# SOC_camera.net
KiCad netlist of a schematic drawn in EAGLE
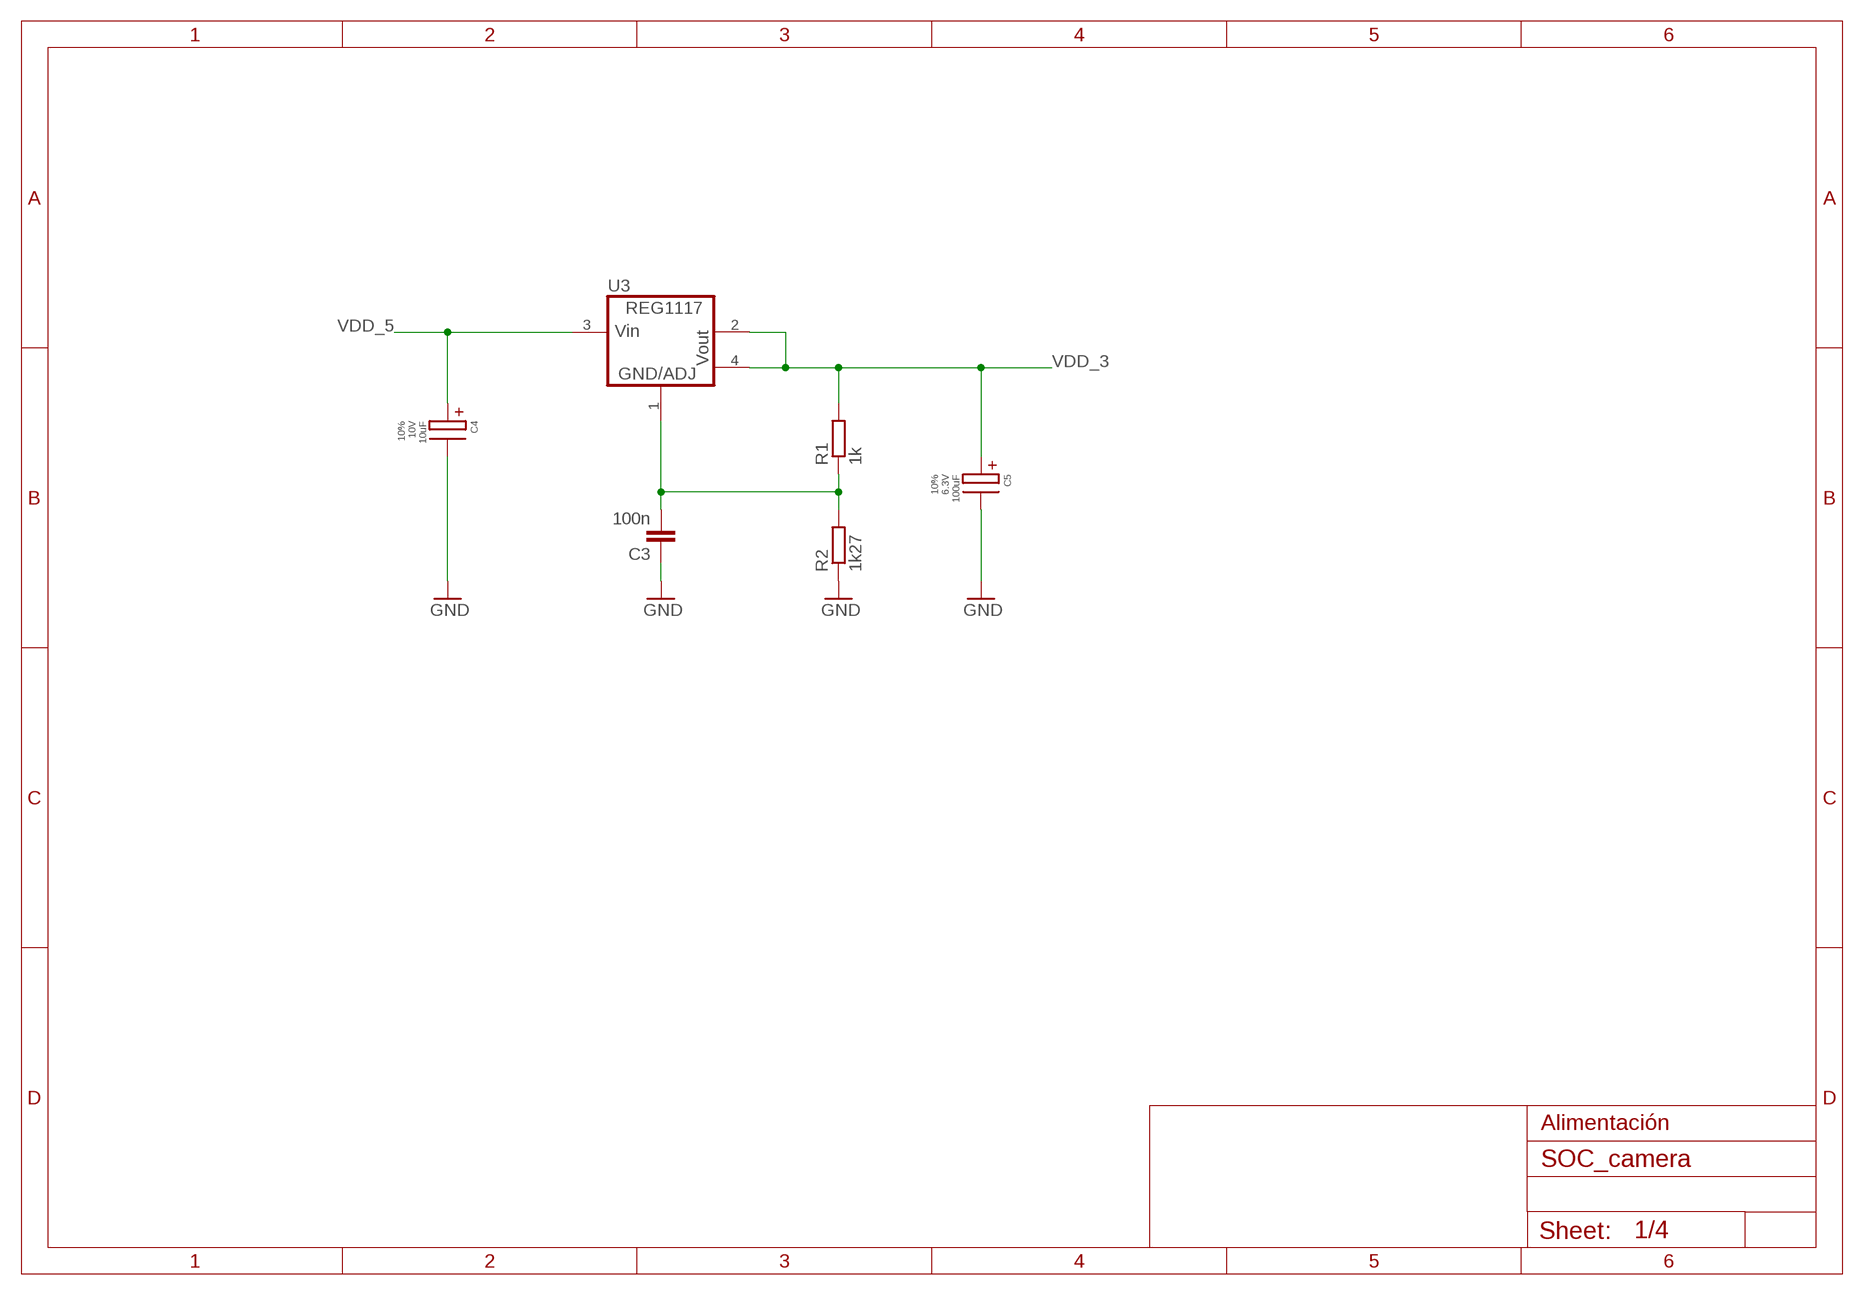
[diagram p0: schematic, sheet 1]
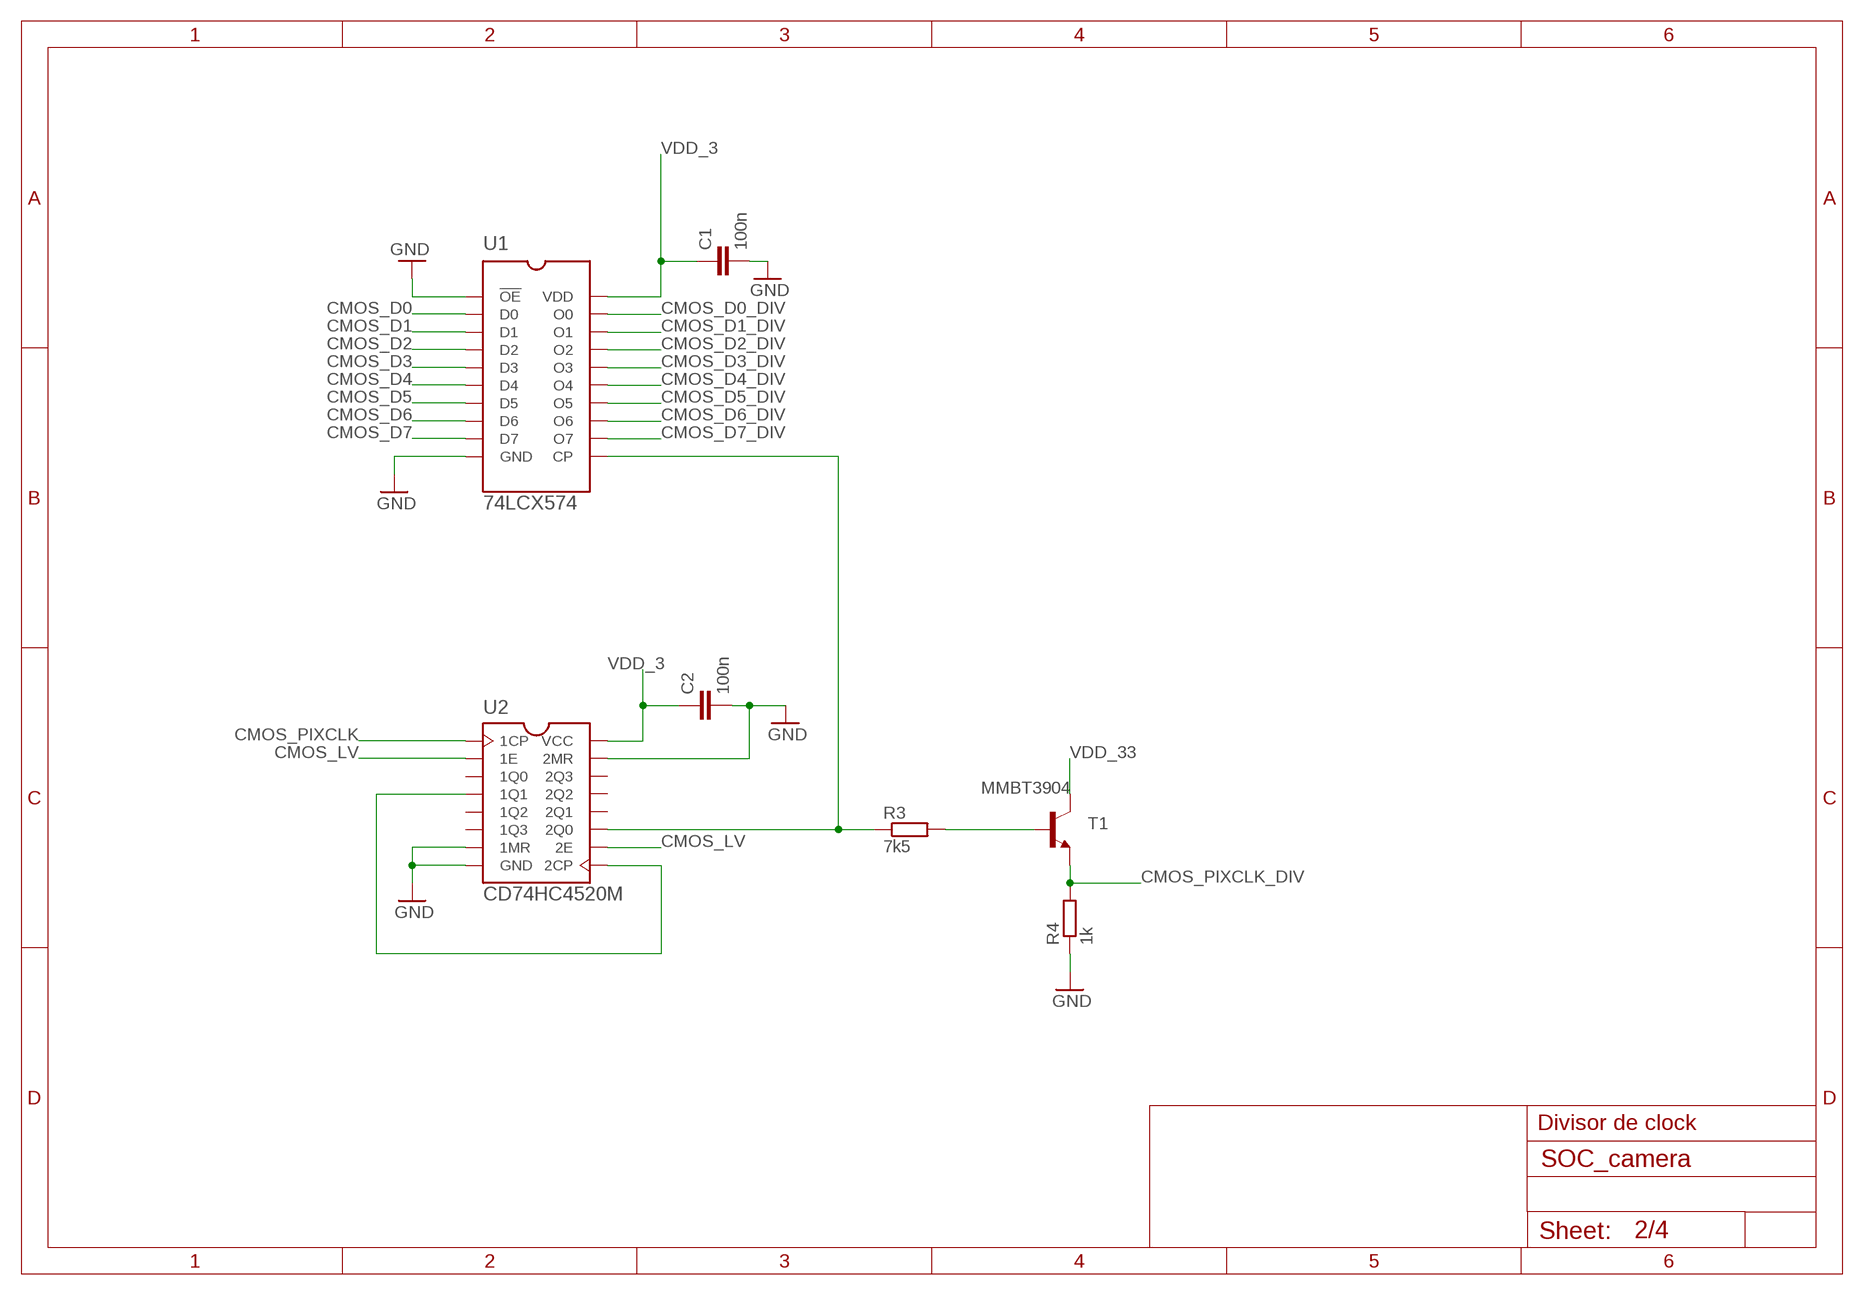
[diagram p1: schematic, sheet 2]
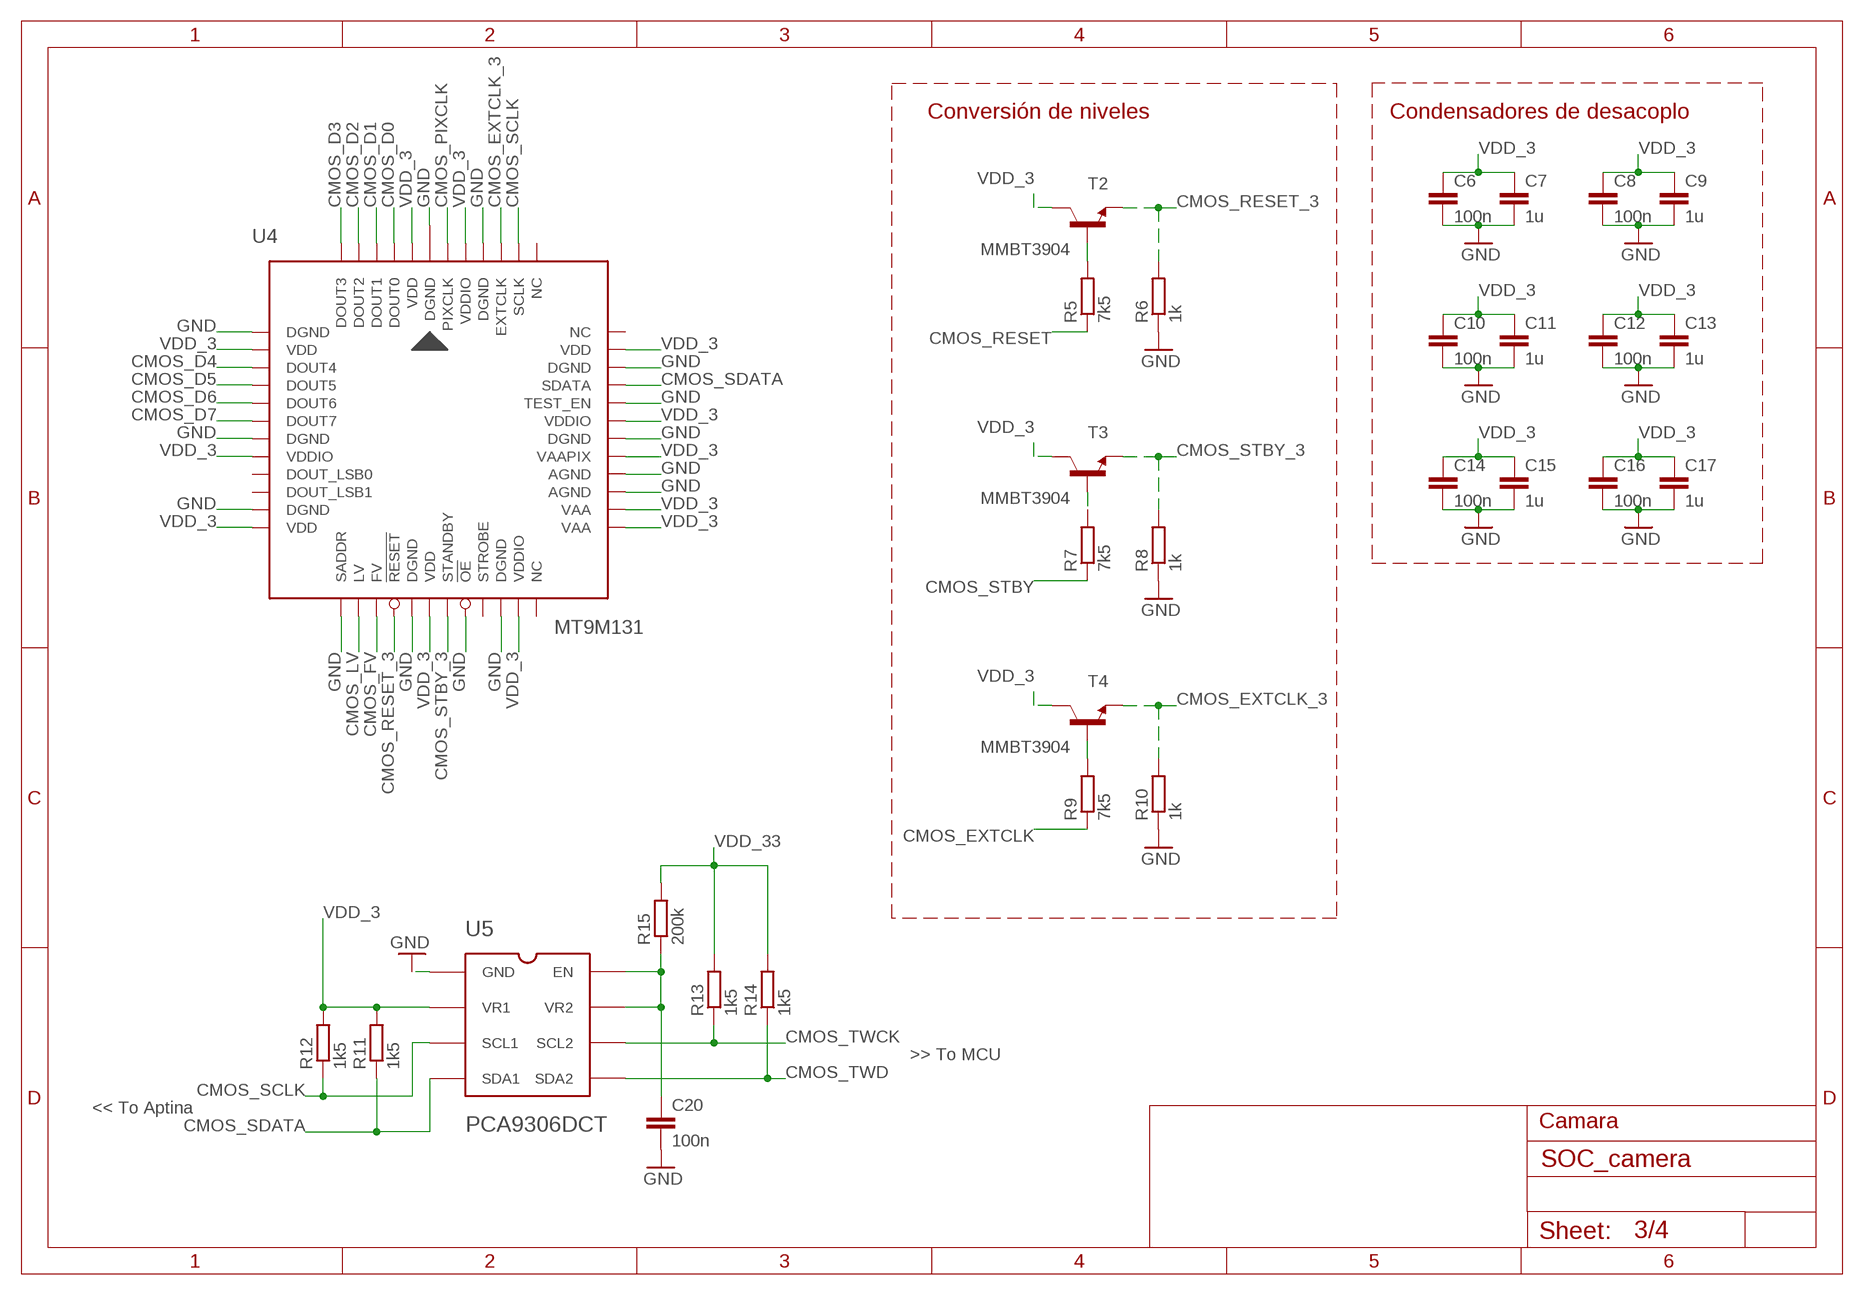
[diagram p2: schematic, sheet 3]
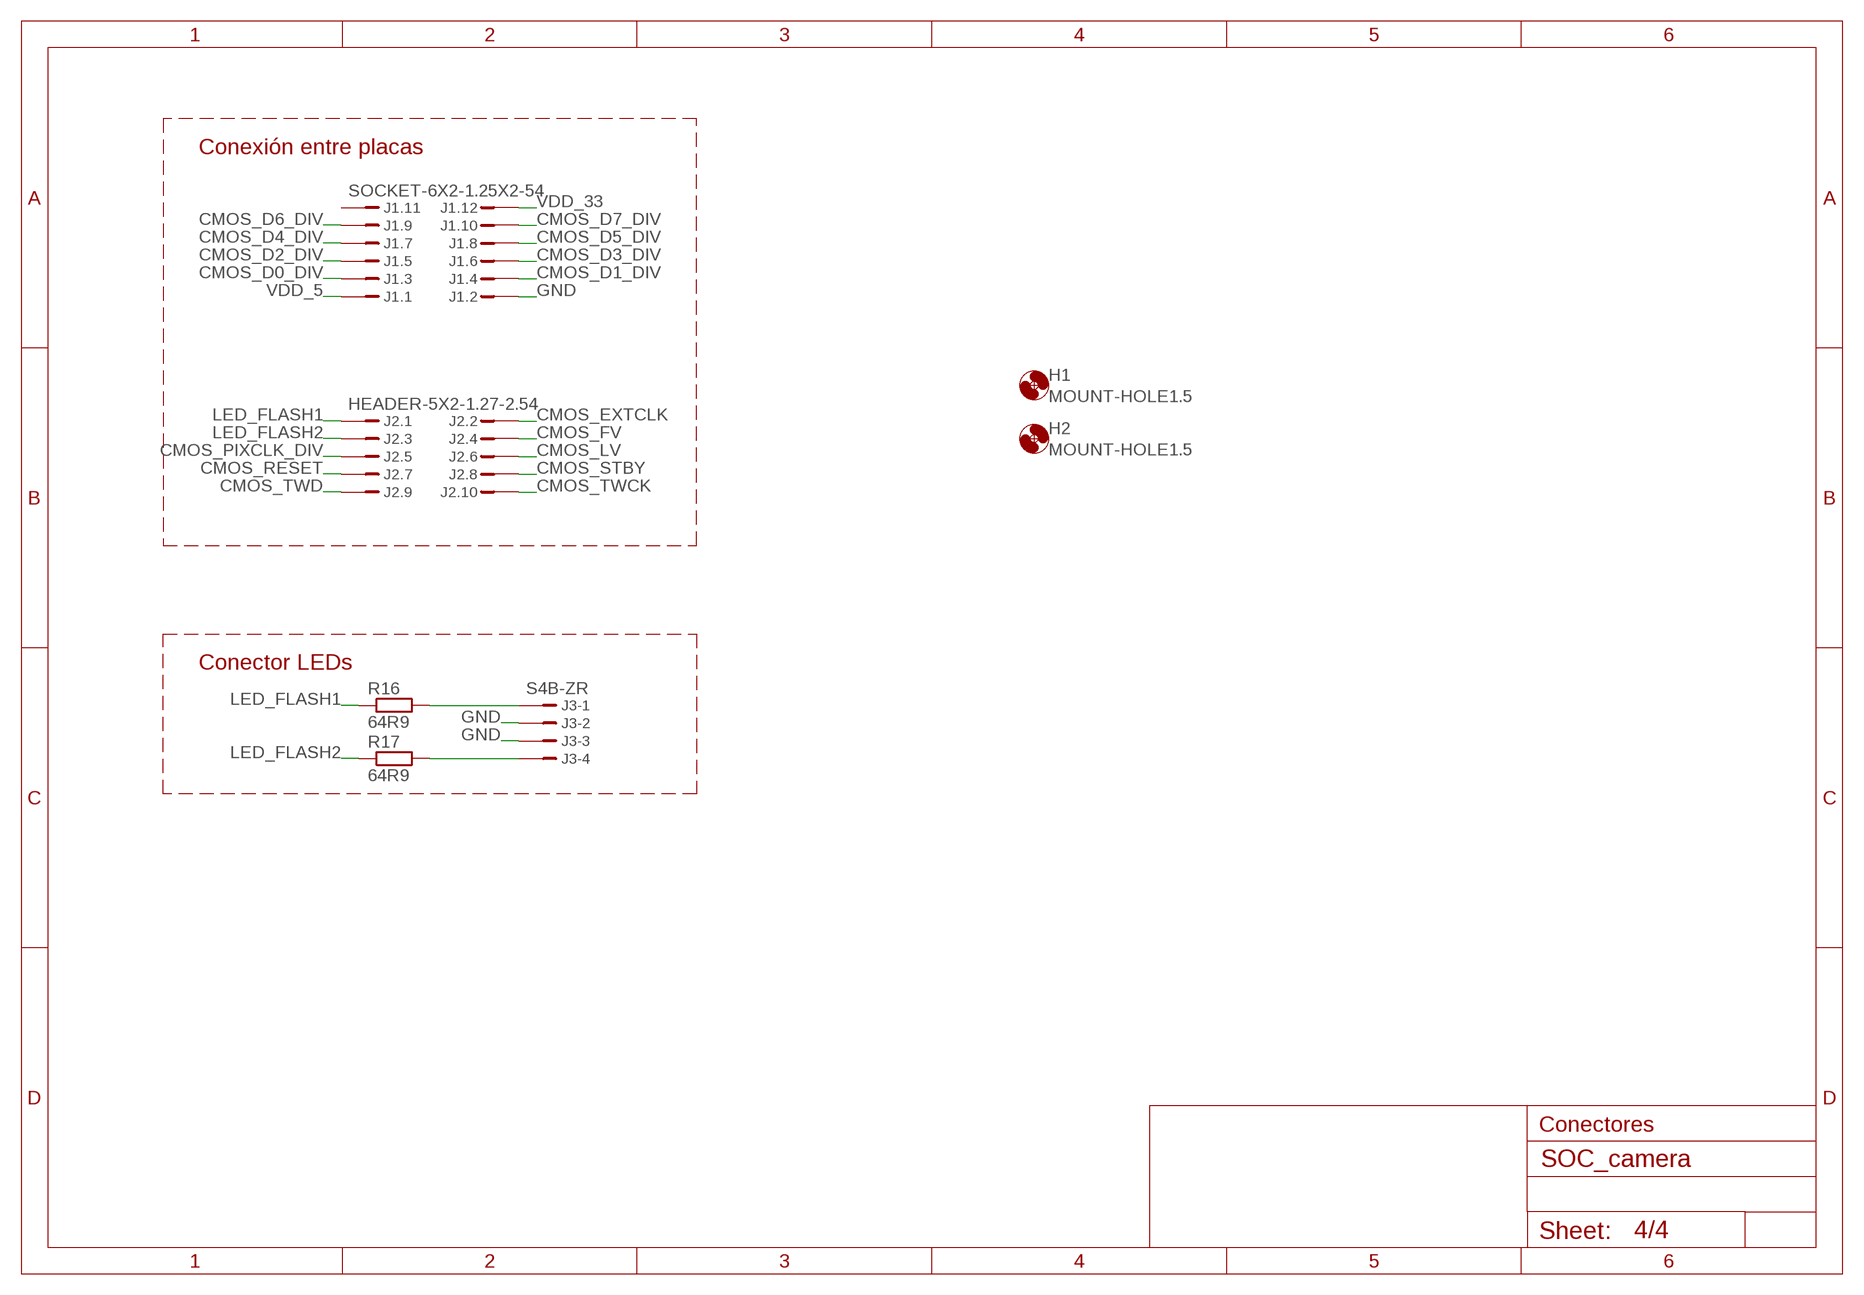
[diagram p3: schematic, sheet 4]

(export (version "E")
  (design (tool "Eeschema 10.0.6"))
  (components
    (comp (ref "C3")
      (value "100n")
      (footprint "eagle-import:C0603")
      (libsource (lib "eagle-import") (part "C-EUC0603"))
    )
    (comp (ref "C4")
      (value "10uF")
      (footprint "eagle-import:3528-21")
      (fields
        (field (name "MPN") "293D106X9010B2TE3")
        (field (name "TOLERANCE") "10%")
        (field (name "VOLTAGE") "10V")
      )
      (libsource (lib "eagle-import") (part "CPOL_TF-B10U-10V-10%-"))
    )
    (comp (ref "C5")
      (value "100uF")
      (footprint "eagle-import:3528-21")
      (fields
        (field (name "MPN") "293D107X96R3B2TE3")
        (field (name "TOLERANCE") "10%")
        (field (name "VOLTAGE") "6.3V")
      )
      (libsource (lib "eagle-import") (part "CPOL_TF-B100U-6V3-10%-"))
    )
    (comp (ref "R1")
      (value "1k")
      (footprint "eagle-import:R0603")
      (libsource (lib "eagle-import") (part "R-EU_R0603"))
    )
    (comp (ref "R2")
      (value "1k27")
      (footprint "eagle-import:R0603")
      (libsource (lib "eagle-import") (part "R-EU_R0603"))
    )
    (comp (ref "U3")
      (value "REG1117")
      (footprint "eagle-import:SOT223")
      (libsource (lib "eagle-import") (part "REG1117"))
    )
    (comp (ref "H1")
      (value "MOUNT-HOLE1.5")
      (footprint "eagle-import:1,5")
      (libsource (lib "eagle-import") (part "MOUNT-HOLE1.5"))
    )
    (comp (ref "H2")
      (value "MOUNT-HOLE1.5")
      (footprint "eagle-import:1,5")
      (libsource (lib "eagle-import") (part "MOUNT-HOLE1.5"))
    )
    (comp (ref "J1")
      (value "SOCKET-6X2-1.25X2-54")
      (footprint "eagle-import:SOCKET-THD-6X2(1.27X2.54)")
      (libsource (lib "eagle-import") (part "SOCKET-6X2-1.25X2-54"))
    )
    (comp (ref "J2")
      (value "HEADER-5X2-1.27-2.54")
      (footprint "eagle-import:HEADER-THD-5X2(1.27X2.54)")
      (libsource (lib "eagle-import") (part "HEADER-5X2-1.27-2.54"))
    )
    (comp (ref "J3")
      (value "S4B-ZR")
      (footprint "eagle-import:S4B-ZR")
      (fields (field (name "MF") "FARNELL") (field (name "MPN") "S4B-ZR(LF)(SN)"))
      (libsource (lib "eagle-import") (part "?4B-ZRS"))
    )
    (comp (ref "R16")
      (value "64R9")
      (footprint "eagle-import:R0603")
      (libsource (lib "eagle-import") (part "R-EU_R0603"))
    )
    (comp (ref "R17")
      (value "64R9")
      (footprint "eagle-import:R0603")
      (libsource (lib "eagle-import") (part "R-EU_R0603"))
    )
    (comp (ref "C1")
      (value "100n")
      (footprint "eagle-import:C0603")
      (libsource (lib "eagle-import") (part "C-EUC0603"))
    )
    (comp (ref "C2")
      (value "100n")
      (footprint "eagle-import:C0603")
      (libsource (lib "eagle-import") (part "C-EUC0603"))
    )
    (comp (ref "R3")
      (value "7k5")
      (footprint "eagle-import:R0603")
      (libsource (lib "eagle-import") (part "resistor_R-EU_R0603"))
    )
    (comp (ref "R4")
      (value "1k")
      (footprint "eagle-import:R0603")
      (libsource (lib "eagle-import") (part "resistor_R-EU_R0603"))
    )
    (comp (ref "T1")
      (value "MMBT3904")
      (footprint "eagle-import:SOT23-BEC")
      (libsource (lib "eagle-import") (part "-NPN-SOT23-BECMMBT3904LT1"))
    )
    (comp (ref "U1")
      (value "74LCX574")
      (footprint "eagle-import:TSSOP20")
      (fields (field (name "MPN") "74LCX574MTCX "))
      (libsource (lib "eagle-import") (part "74LCX574"))
    )
    (comp (ref "U2")
      (value "CD74HC4520M")
      (footprint "eagle-import:SOP16")
      (libsource (lib "eagle-import") (part "CD74HC4520M"))
    )
    (comp (ref "C6")
      (value "100n")
      (footprint "eagle-import:C0402")
      (libsource (lib "eagle-import") (part "C-EUC0402"))
    )
    (comp (ref "C7")
      (value "1u")
      (footprint "eagle-import:C0402")
      (libsource (lib "eagle-import") (part "C-EUC0402"))
    )
    (comp (ref "C8")
      (value "100n")
      (footprint "eagle-import:C0402")
      (libsource (lib "eagle-import") (part "C-EUC0402"))
    )
    (comp (ref "C9")
      (value "1u")
      (footprint "eagle-import:C0402")
      (libsource (lib "eagle-import") (part "C-EUC0402"))
    )
    (comp (ref "C10")
      (value "100n")
      (footprint "eagle-import:C0402")
      (libsource (lib "eagle-import") (part "C-EUC0402"))
    )
    (comp (ref "C11")
      (value "1u")
      (footprint "eagle-import:C0402")
      (libsource (lib "eagle-import") (part "C-EUC0402"))
    )
    (comp (ref "C12")
      (value "100n")
      (footprint "eagle-import:C0402")
      (libsource (lib "eagle-import") (part "C-EUC0402"))
    )
    (comp (ref "C13")
      (value "1u")
      (footprint "eagle-import:C0402")
      (libsource (lib "eagle-import") (part "C-EUC0402"))
    )
    (comp (ref "C14")
      (value "100n")
      (footprint "eagle-import:C0402")
      (libsource (lib "eagle-import") (part "C-EUC0402"))
    )
    (comp (ref "C15")
      (value "1u")
      (footprint "eagle-import:C0402")
      (libsource (lib "eagle-import") (part "C-EUC0402"))
    )
    (comp (ref "C16")
      (value "100n")
      (footprint "eagle-import:C0402")
      (libsource (lib "eagle-import") (part "C-EUC0402"))
    )
    (comp (ref "C17")
      (value "1u")
      (footprint "eagle-import:C0402")
      (libsource (lib "eagle-import") (part "C-EUC0402"))
    )
    (comp (ref "C20")
      (value "100n")
      (footprint "eagle-import:C0402")
      (libsource (lib "eagle-import") (part "C-EUC0402"))
    )
    (comp (ref "R5")
      (value "7k5")
      (footprint "eagle-import:R0603")
      (libsource (lib "eagle-import") (part "R-EU_R0603"))
    )
    (comp (ref "R6")
      (value "1k")
      (footprint "eagle-import:R0603")
      (libsource (lib "eagle-import") (part "R-EU_R0603"))
    )
    (comp (ref "R7")
      (value "7k5")
      (footprint "eagle-import:R0603")
      (libsource (lib "eagle-import") (part "R-EU_R0603"))
    )
    (comp (ref "R8")
      (value "1k")
      (footprint "eagle-import:R0603")
      (libsource (lib "eagle-import") (part "R-EU_R0603"))
    )
    (comp (ref "R9")
      (value "7k5")
      (footprint "eagle-import:R0603")
      (libsource (lib "eagle-import") (part "R-EU_R0603"))
    )
    (comp (ref "R10")
      (value "1k")
      (footprint "eagle-import:R0603")
      (libsource (lib "eagle-import") (part "R-EU_R0603"))
    )
    (comp (ref "R11")
      (value "1k5")
      (footprint "eagle-import:R0402")
      (libsource (lib "eagle-import") (part "R-EU_R0402"))
    )
    (comp (ref "R12")
      (value "1k5")
      (footprint "eagle-import:R0402")
      (libsource (lib "eagle-import") (part "R-EU_R0402"))
    )
    (comp (ref "R13")
      (value "1k5")
      (footprint "eagle-import:R0402")
      (libsource (lib "eagle-import") (part "R-EU_R0402"))
    )
    (comp (ref "R14")
      (value "1k5")
      (footprint "eagle-import:R0402")
      (libsource (lib "eagle-import") (part "R-EU_R0402"))
    )
    (comp (ref "R15")
      (value "200k")
      (footprint "eagle-import:R0402")
      (libsource (lib "eagle-import") (part "R-EU_R0402"))
    )
    (comp (ref "T2")
      (value "MMBT3904")
      (footprint "eagle-import:SOT23-BEC")
      (libsource (lib "eagle-import") (part "-NPN-SOT23-BECMMBT3904LT1"))
    )
    (comp (ref "T3")
      (value "MMBT3904")
      (footprint "eagle-import:SOT23-BEC")
      (libsource (lib "eagle-import") (part "-NPN-SOT23-BECMMBT3904LT1"))
    )
    (comp (ref "T4")
      (value "MMBT3904")
      (footprint "eagle-import:SOT23-BEC")
      (libsource (lib "eagle-import") (part "-NPN-SOT23-BECMMBT3904LT1"))
    )
    (comp (ref "U4")
      (value "MT9M131")
      (footprint "eagle-import:APTINA")
      (fields (field (name "MPN") "MT9M131C12STC "))
      (libsource (lib "eagle-import") (part "MT9M131"))
    )
    (comp (ref "U5")
      (value "PCA9306DCT")
      (footprint "eagle-import:SSOP8")
      (fields
        (field (name "MPN") "PCA9306DCTR")
        (field (name "MPN_1") "PCA9306DCTR")
        (field (name "OC_FARNELL") "1470936")
        (field (name "OC_RS") "662-7415")
      )
      (libsource (lib "eagle-import") (part "PCA9306DCT"))
    )
  )
  (nets
    (net (code "1") (name "CMOS_D0") (class "Default")
      (node (ref "U1") (pin "2") (pinfunction "D0_2") (pintype "bidirectional"))
      (node (ref "U4") (pin "3") (pinfunction "DOUT0_3") (pintype "bidirectional"))
    )
    (net (code "2") (name "CMOS_D0_DIV") (class "Default")
      (node (ref "J1") (pin "P3") (pinfunction "1_P3") (pintype "passive"))
      (node (ref "U1") (pin "19") (pinfunction "O0_19") (pintype "bidirectional"))
    )
    (net (code "3") (name "CMOS_D1") (class "Default")
      (node (ref "U1") (pin "3") (pinfunction "D1_3") (pintype "bidirectional"))
      (node (ref "U4") (pin "4") (pinfunction "DOUT1_4") (pintype "bidirectional"))
    )
    (net (code "4") (name "CMOS_D1_DIV") (class "Default")
      (node (ref "J1") (pin "P4") (pinfunction "1_P4") (pintype "passive"))
      (node (ref "U1") (pin "18") (pinfunction "O1_18") (pintype "bidirectional"))
    )
    (net (code "5") (name "CMOS_D2") (class "Default")
      (node (ref "U1") (pin "4") (pinfunction "D2_4") (pintype "bidirectional"))
      (node (ref "U4") (pin "5") (pinfunction "DOUT2_5") (pintype "bidirectional"))
    )
    (net (code "6") (name "CMOS_D2_DIV") (class "Default")
      (node (ref "J1") (pin "P5") (pinfunction "1_P5") (pintype "passive"))
      (node (ref "U1") (pin "17") (pinfunction "O2_17") (pintype "bidirectional"))
    )
    (net (code "7") (name "CMOS_D3") (class "Default")
      (node (ref "U1") (pin "5") (pinfunction "D3_5") (pintype "bidirectional"))
      (node (ref "U4") (pin "6") (pinfunction "DOUT3_6") (pintype "bidirectional"))
    )
    (net (code "8") (name "CMOS_D3_DIV") (class "Default")
      (node (ref "J1") (pin "P6") (pinfunction "1_P6") (pintype "passive"))
      (node (ref "U1") (pin "16") (pinfunction "O3_16") (pintype "bidirectional"))
    )
    (net (code "9") (name "CMOS_D4") (class "Default")
      (node (ref "U1") (pin "6") (pinfunction "D4_6") (pintype "bidirectional"))
      (node (ref "U4") (pin "9") (pinfunction "DOUT4_9") (pintype "bidirectional"))
    )
    (net (code "10") (name "CMOS_D4_DIV") (class "Default")
      (node (ref "J1") (pin "P7") (pinfunction "1_P7") (pintype "passive"))
      (node (ref "U1") (pin "15") (pinfunction "O4_15") (pintype "bidirectional"))
    )
    (net (code "11") (name "CMOS_D5") (class "Default")
      (node (ref "U1") (pin "7") (pinfunction "D5_7") (pintype "bidirectional"))
      (node (ref "U4") (pin "10") (pinfunction "DOUT5_10") (pintype "bidirectional"))
    )
    (net (code "12") (name "CMOS_D5_DIV") (class "Default")
      (node (ref "J1") (pin "P8") (pinfunction "1_P8") (pintype "passive"))
      (node (ref "U1") (pin "14") (pinfunction "O5_14") (pintype "bidirectional"))
    )
    (net (code "13") (name "CMOS_D6") (class "Default")
      (node (ref "U1") (pin "8") (pinfunction "D6_8") (pintype "bidirectional"))
      (node (ref "U4") (pin "11") (pinfunction "DOUT6_11") (pintype "bidirectional"))
    )
    (net (code "14") (name "CMOS_D6_DIV") (class "Default")
      (node (ref "J1") (pin "P9") (pinfunction "1_P9") (pintype "passive"))
      (node (ref "U1") (pin "13") (pinfunction "O6_13") (pintype "bidirectional"))
    )
    (net (code "15") (name "CMOS_D7") (class "Default")
      (node (ref "U1") (pin "9") (pinfunction "D7_9") (pintype "bidirectional"))
      (node (ref "U4") (pin "12") (pinfunction "DOUT7_12") (pintype "bidirectional"))
    )
    (net (code "16") (name "CMOS_D7_DIV") (class "Default")
      (node (ref "J1") (pin "P10") (pinfunction "1_P10") (pintype "passive"))
      (node (ref "U1") (pin "12") (pinfunction "O7_12") (pintype "bidirectional"))
    )
    (net (code "17") (name "CMOS_EXTCLK") (class "Default")
      (node (ref "J2") (pin "2") (pinfunction "1_2") (pintype "passive"))
      (node (ref "R9") (pin "1") (pinfunction "1_1") (pintype "passive"))
    )
    (net (code "18") (name "CMOS_EXTCLK_3") (class "Default")
      (node (ref "R10") (pin "2") (pinfunction "2_2") (pintype "passive"))
      (node (ref "T4") (pin "E") (pinfunction "E_E") (pintype "passive"))
      (node (ref "U4") (pin "45") (pinfunction "EXTCLK_45") (pintype "bidirectional"))
    )
    (net (code "19") (name "CMOS_FV") (class "Default")
      (node (ref "J2") (pin "4") (pinfunction "1_4") (pintype "passive"))
      (node (ref "U4") (pin "21") (pinfunction "FV_21") (pintype "bidirectional"))
    )
    (net (code "20") (name "CMOS_LV") (class "Default")
      (node (ref "J2") (pin "6") (pinfunction "1_6") (pintype "passive"))
      (node (ref "U2") (pin "10") (pinfunction "2E_10") (pintype "bidirectional"))
      (node (ref "U2") (pin "2") (pinfunction "1E_2") (pintype "bidirectional"))
      (node (ref "U4") (pin "20") (pinfunction "LV_20") (pintype "bidirectional"))
    )
    (net (code "21") (name "CMOS_PIXCLK") (class "Default")
      (node (ref "U2") (pin "1") (pinfunction "1CP_1") (pintype "bidirectional"))
      (node (ref "U4") (pin "48") (pinfunction "PIXCLK_48") (pintype "bidirectional"))
    )
    (net (code "22") (name "CMOS_PIXCLK_DIV") (class "Default")
      (node (ref "J2") (pin "5") (pinfunction "1_5") (pintype "passive"))
      (node (ref "R4") (pin "2") (pinfunction "2_2") (pintype "passive"))
      (node (ref "T1") (pin "E") (pinfunction "E_E") (pintype "passive"))
    )
    (net (code "23") (name "CMOS_RESET") (class "Default")
      (node (ref "J2") (pin "7") (pinfunction "1_7") (pintype "passive"))
      (node (ref "R5") (pin "1") (pinfunction "1_1") (pintype "passive"))
    )
    (net (code "24") (name "CMOS_RESET_3") (class "Default")
      (node (ref "R6") (pin "2") (pinfunction "2_2") (pintype "passive"))
      (node (ref "T2") (pin "E") (pinfunction "E_E") (pintype "passive"))
      (node (ref "U4") (pin "22") (pinfunction "~{RESET}_22") (pintype "bidirectional"))
    )
    (net (code "25") (name "CMOS_SCLK") (class "Default")
      (node (ref "R12") (pin "1") (pinfunction "1_1") (pintype "passive"))
      (node (ref "U4") (pin "44") (pinfunction "SCLK_44") (pintype "bidirectional"))
      (node (ref "U5") (pin "3") (pinfunction "SCL1_3") (pintype "bidirectional"))
    )
    (net (code "26") (name "CMOS_SDATA") (class "Default")
      (node (ref "R11") (pin "1") (pinfunction "1_1") (pintype "passive"))
      (node (ref "U4") (pin "39") (pinfunction "SDATA_39") (pintype "bidirectional"))
      (node (ref "U5") (pin "4") (pinfunction "SDA1_4") (pintype "bidirectional"))
    )
    (net (code "27") (name "CMOS_STBY") (class "Default")
      (node (ref "J2") (pin "8") (pinfunction "1_8") (pintype "passive"))
      (node (ref "R7") (pin "1") (pinfunction "1_1") (pintype "passive"))
    )
    (net (code "28") (name "CMOS_STBY_3") (class "Default")
      (node (ref "R8") (pin "2") (pinfunction "2_2") (pintype "passive"))
      (node (ref "T3") (pin "E") (pinfunction "E_E") (pintype "passive"))
      (node (ref "U4") (pin "25") (pinfunction "STANDBY_25") (pintype "bidirectional"))
    )
    (net (code "29") (name "CMOS_TWCK") (class "Default")
      (node (ref "J2") (pin "10") (pinfunction "1_10") (pintype "passive"))
      (node (ref "R13") (pin "1") (pinfunction "1_1") (pintype "passive"))
      (node (ref "U5") (pin "6") (pinfunction "SCL2_6") (pintype "bidirectional"))
    )
    (net (code "30") (name "CMOS_TWD") (class "Default")
      (node (ref "J2") (pin "9") (pinfunction "1_9") (pintype "passive"))
      (node (ref "R14") (pin "1") (pinfunction "1_1") (pintype "passive"))
      (node (ref "U5") (pin "5") (pinfunction "SDA2_5") (pintype "bidirectional"))
    )
    (net (code "31") (name "GND") (class "Default")
      (node (ref "C1") (pin "2") (pinfunction "2_2") (pintype "passive"))
      (node (ref "C10") (pin "2") (pinfunction "2_2") (pintype "passive"))
      (node (ref "C11") (pin "2") (pinfunction "2_2") (pintype "passive"))
      (node (ref "C12") (pin "2") (pinfunction "2_2") (pintype "passive"))
      (node (ref "C13") (pin "2") (pinfunction "2_2") (pintype "passive"))
      (node (ref "C14") (pin "2") (pinfunction "2_2") (pintype "passive"))
      (node (ref "C15") (pin "2") (pinfunction "2_2") (pintype "passive"))
      (node (ref "C16") (pin "2") (pinfunction "2_2") (pintype "passive"))
      (node (ref "C17") (pin "2") (pinfunction "2_2") (pintype "passive"))
      (node (ref "C2") (pin "2") (pinfunction "2_2") (pintype "passive"))
      (node (ref "C20") (pin "2") (pinfunction "2_2") (pintype "passive"))
      (node (ref "C3") (pin "1") (pinfunction "1_1") (pintype "passive"))
      (node (ref "C4") (pin "NEG") (pinfunction "NEG_NEG") (pintype "bidirectional"))
      (node (ref "C5") (pin "NEG") (pinfunction "NEG_NEG") (pintype "bidirectional"))
      (node (ref "C6") (pin "2") (pinfunction "2_2") (pintype "passive"))
      (node (ref "C7") (pin "2") (pinfunction "2_2") (pintype "passive"))
      (node (ref "C8") (pin "2") (pinfunction "2_2") (pintype "passive"))
      (node (ref "C9") (pin "2") (pinfunction "2_2") (pintype "passive"))
      (node (ref "J1") (pin "P2") (pinfunction "1_P2") (pintype "passive"))
      (node (ref "J3") (pin "2") (pinfunction "1_2") (pintype "passive"))
      (node (ref "J3") (pin "3") (pinfunction "1_3") (pintype "passive"))
      (node (ref "R10") (pin "1") (pinfunction "1_1") (pintype "passive"))
      (node (ref "R2") (pin "1") (pinfunction "1_1") (pintype "passive"))
      (node (ref "R4") (pin "1") (pinfunction "1_1") (pintype "passive"))
      (node (ref "R6") (pin "1") (pinfunction "1_1") (pintype "passive"))
      (node (ref "R8") (pin "1") (pinfunction "1_1") (pintype "passive"))
      (node (ref "U1") (pin "1") (pinfunction "~{OE}_1") (pintype "bidirectional"))
      (node (ref "U1") (pin "10") (pinfunction "GND_10") (pintype "bidirectional"))
      (node (ref "U2") (pin "15") (pinfunction "2MR_15") (pintype "bidirectional"))
      (node (ref "U2") (pin "7") (pinfunction "1MR_7") (pintype "bidirectional"))
      (node (ref "U2") (pin "8") (pinfunction "GND_8") (pintype "bidirectional"))
      (node (ref "U4") (pin "1") (pinfunction "DGND_1") (pintype "bidirectional"))
      (node (ref "U4") (pin "13") (pinfunction "DGND_13") (pintype "bidirectional"))
      (node (ref "U4") (pin "17") (pinfunction "DGND_17") (pintype "bidirectional"))
      (node (ref "U4") (pin "19") (pinfunction "SADDR_19") (pintype "bidirectional"))
      (node (ref "U4") (pin "23") (pinfunction "DGND_23") (pintype "bidirectional"))
      (node (ref "U4") (pin "26") (pinfunction "~{OE}_26") (pintype "bidirectional"))
      (node (ref "U4") (pin "28") (pinfunction "DGND_28") (pintype "bidirectional"))
      (node (ref "U4") (pin "33") (pinfunction "AGND_33") (pintype "bidirectional"))
      (node (ref "U4") (pin "34") (pinfunction "AGND_34") (pintype "bidirectional"))
      (node (ref "U4") (pin "36") (pinfunction "DGND_36") (pintype "bidirectional"))
      (node (ref "U4") (pin "38") (pinfunction "TEST_EN_38") (pintype "bidirectional"))
      (node (ref "U4") (pin "40") (pinfunction "DGND_40") (pintype "bidirectional"))
      (node (ref "U4") (pin "46") (pinfunction "DGND_46") (pintype "bidirectional"))
      (node (ref "U4") (pin "7") (pinfunction "DGND_7") (pintype "bidirectional"))
      (node (ref "U5") (pin "1") (pinfunction "GND_1") (pintype "bidirectional"))
    )
    (net (code "32") (name "LED_FLASH1") (class "Default")
      (node (ref "J2") (pin "1") (pinfunction "1_1") (pintype "passive"))
      (node (ref "R16") (pin "1") (pinfunction "1_1") (pintype "passive"))
    )
    (net (code "33") (name "LED_FLASH2") (class "Default")
      (node (ref "J2") (pin "3") (pinfunction "1_3") (pintype "passive"))
      (node (ref "R17") (pin "1") (pinfunction "1_1") (pintype "passive"))
    )
    (net (code "34") (name "Net-(J3-Pad1)") (class "Default")
      (node (ref "J3") (pin "1") (pinfunction "1_1") (pintype "passive"))
      (node (ref "R16") (pin "2") (pinfunction "2_2") (pintype "passive"))
    )
    (net (code "35") (name "Net-(J3D-1)") (class "Default")
      (node (ref "J3") (pin "4") (pinfunction "1_4") (pintype "passive"))
      (node (ref "R17") (pin "2") (pinfunction "2_2") (pintype "passive"))
    )
    (net (code "36") (name "Net-(R3-Pad2)") (class "Default")
      (node (ref "R3") (pin "2") (pinfunction "2_2") (pintype "passive"))
      (node (ref "T1") (pin "B") (pinfunction "B_B") (pintype "passive"))
    )
    (net (code "37") (name "Net-(R5-Pad2)") (class "Default")
      (node (ref "R5") (pin "2") (pinfunction "2_2") (pintype "passive"))
      (node (ref "T2") (pin "B") (pinfunction "B_B") (pintype "passive"))
    )
    (net (code "38") (name "Net-(R7-Pad2)") (class "Default")
      (node (ref "R7") (pin "2") (pinfunction "2_2") (pintype "passive"))
      (node (ref "T3") (pin "B") (pinfunction "B_B") (pintype "passive"))
    )
    (net (code "39") (name "Net-(R9-Pad2)") (class "Default")
      (node (ref "R9") (pin "2") (pinfunction "2_2") (pintype "passive"))
      (node (ref "T4") (pin "B") (pinfunction "B_B") (pintype "passive"))
    )
    (net (code "40") (name "Net-(U1-CP)") (class "Default")
      (node (ref "R3") (pin "1") (pinfunction "1_1") (pintype "passive"))
      (node (ref "U1") (pin "11") (pinfunction "CP_11") (pintype "bidirectional"))
      (node (ref "U2") (pin "11") (pinfunction "2Q0_11") (pintype "bidirectional"))
    )
    (net (code "41") (name "Net-(U2-1Q1)") (class "Default")
      (node (ref "U2") (pin "4") (pinfunction "1Q1_4") (pintype "bidirectional"))
      (node (ref "U2") (pin "9") (pinfunction "2CP_9") (pintype "bidirectional"))
    )
    (net (code "42") (name "Net-(U3-GND)") (class "Default")
      (node (ref "C3") (pin "2") (pinfunction "2_2") (pintype "passive"))
      (node (ref "R1") (pin "1") (pinfunction "1_1") (pintype "passive"))
      (node (ref "R2") (pin "2") (pinfunction "2_2") (pintype "passive"))
      (node (ref "U3") (pin "1") (pinfunction "GND_1") (pintype "bidirectional"))
    )
    (net (code "43") (name "Net-(U5-EN)") (class "Default")
      (node (ref "C20") (pin "1") (pinfunction "1_1") (pintype "passive"))
      (node (ref "R15") (pin "1") (pinfunction "1_1") (pintype "passive"))
      (node (ref "U5") (pin "7") (pinfunction "VR2_7") (pintype "bidirectional"))
      (node (ref "U5") (pin "8") (pinfunction "EN_8") (pintype "bidirectional"))
    )
    (net (code "44") (name "VDD_3") (class "Default")
      (node (ref "C1") (pin "1") (pinfunction "1_1") (pintype "passive"))
      (node (ref "C10") (pin "1") (pinfunction "1_1") (pintype "passive"))
      (node (ref "C11") (pin "1") (pinfunction "1_1") (pintype "passive"))
      (node (ref "C12") (pin "1") (pinfunction "1_1") (pintype "passive"))
      (node (ref "C13") (pin "1") (pinfunction "1_1") (pintype "passive"))
      (node (ref "C14") (pin "1") (pinfunction "1_1") (pintype "passive"))
      (node (ref "C15") (pin "1") (pinfunction "1_1") (pintype "passive"))
      (node (ref "C16") (pin "1") (pinfunction "1_1") (pintype "passive"))
      (node (ref "C17") (pin "1") (pinfunction "1_1") (pintype "passive"))
      (node (ref "C2") (pin "1") (pinfunction "1_1") (pintype "passive"))
      (node (ref "C5") (pin "POS") (pinfunction "POS_POS") (pintype "bidirectional"))
      (node (ref "C6") (pin "1") (pinfunction "1_1") (pintype "passive"))
      (node (ref "C7") (pin "1") (pinfunction "1_1") (pintype "passive"))
      (node (ref "C8") (pin "1") (pinfunction "1_1") (pintype "passive"))
      (node (ref "C9") (pin "1") (pinfunction "1_1") (pintype "passive"))
      (node (ref "R1") (pin "2") (pinfunction "2_2") (pintype "passive"))
      (node (ref "R11") (pin "2") (pinfunction "2_2") (pintype "passive"))
      (node (ref "R12") (pin "2") (pinfunction "2_2") (pintype "passive"))
      (node (ref "T2") (pin "C") (pinfunction "C_C") (pintype "passive"))
      (node (ref "T3") (pin "C") (pinfunction "C_C") (pintype "passive"))
      (node (ref "T4") (pin "C") (pinfunction "C_C") (pintype "passive"))
      (node (ref "U1") (pin "20") (pinfunction "VDD_20") (pintype "bidirectional"))
      (node (ref "U2") (pin "16") (pinfunction "VCC_16") (pintype "bidirectional"))
      (node (ref "U3") (pin "2") (pinfunction "VOUT_2") (pintype "bidirectional"))
      (node (ref "U3") (pin "4") (pinfunction "VO2_4") (pintype "bidirectional"))
      (node (ref "U4") (pin "14") (pinfunction "VDDIO_14") (pintype "bidirectional"))
      (node (ref "U4") (pin "18") (pinfunction "VDD_18") (pintype "bidirectional"))
      (node (ref "U4") (pin "2") (pinfunction "VDD_2") (pintype "bidirectional"))
      (node (ref "U4") (pin "24") (pinfunction "VDD_24") (pintype "bidirectional"))
      (node (ref "U4") (pin "29") (pinfunction "VDDIO_29") (pintype "bidirectional"))
      (node (ref "U4") (pin "31") (pinfunction "VAA_31") (pintype "bidirectional"))
      (node (ref "U4") (pin "32") (pinfunction "VAA_32") (pintype "bidirectional"))
      (node (ref "U4") (pin "35") (pinfunction "VAAPIX_35") (pintype "bidirectional"))
      (node (ref "U4") (pin "37") (pinfunction "VDDIO_37") (pintype "bidirectional"))
      (node (ref "U4") (pin "41") (pinfunction "VDD_41") (pintype "bidirectional"))
      (node (ref "U4") (pin "47") (pinfunction "VDDIO_47") (pintype "bidirectional"))
      (node (ref "U4") (pin "8") (pinfunction "VDD_8") (pintype "bidirectional"))
      (node (ref "U5") (pin "2") (pinfunction "VR1_2") (pintype "bidirectional"))
    )
    (net (code "45") (name "VDD_5") (class "Default")
      (node (ref "C4") (pin "POS") (pinfunction "POS_POS") (pintype "bidirectional"))
      (node (ref "J1") (pin "P1") (pinfunction "1_P1") (pintype "passive"))
      (node (ref "U3") (pin "3") (pinfunction "VIN_3") (pintype "input"))
    )
    (net (code "46") (name "VDD_33") (class "Default")
      (node (ref "J1") (pin "P12") (pinfunction "1_P12") (pintype "passive"))
      (node (ref "R13") (pin "2") (pinfunction "2_2") (pintype "passive"))
      (node (ref "R14") (pin "2") (pinfunction "2_2") (pintype "passive"))
      (node (ref "R15") (pin "2") (pinfunction "2_2") (pintype "passive"))
      (node (ref "T1") (pin "C") (pinfunction "C_C") (pintype "passive"))
    )
    (net (code "47") (name "unconnected-(J1C-1-PadP11)") (class "Default")
      (node (ref "J1") (pin "P11") (pinfunction "1_P11") (pintype "passive"))
    )
    (net (code "48") (name "unconnected-(U2-1Q0-Pad3)") (class "Default")
      (node (ref "U2") (pin "3") (pinfunction "1Q0_3") (pintype "bidirectional"))
    )
    (net (code "49") (name "unconnected-(U2-1Q2-Pad5)") (class "Default")
      (node (ref "U2") (pin "5") (pinfunction "1Q2_5") (pintype "bidirectional"))
    )
    (net (code "50") (name "unconnected-(U2-1Q3-Pad6)") (class "Default")
      (node (ref "U2") (pin "6") (pinfunction "1Q3_6") (pintype "bidirectional"))
    )
    (net (code "51") (name "unconnected-(U2-2Q1-Pad12)") (class "Default")
      (node (ref "U2") (pin "12") (pinfunction "2Q1_12") (pintype "bidirectional"))
    )
    (net (code "52") (name "unconnected-(U2-2Q2-Pad13)") (class "Default")
      (node (ref "U2") (pin "13") (pinfunction "2Q2_13") (pintype "bidirectional"))
    )
    (net (code "53") (name "unconnected-(U2-2Q3-Pad14)") (class "Default")
      (node (ref "U2") (pin "14") (pinfunction "2Q3_14") (pintype "bidirectional"))
    )
    (net (code "54") (name "unconnected-(U4-DOUT_LSB0-Pad15)") (class "Default")
      (node (ref "U4") (pin "15") (pinfunction "DOUT_LSB0_15") (pintype "bidirectional"))
    )
    (net (code "55") (name "unconnected-(U4-DOUT_LSB1-Pad16)") (class "Default")
      (node (ref "U4") (pin "16") (pinfunction "DOUT_LSB1_16") (pintype "bidirectional"))
    )
    (net (code "56") (name "unconnected-(U4-NC-Pad30)") (class "Default")
      (node (ref "U4") (pin "30") (pinfunction "NC_30") (pintype "no_connect"))
    )
    (net (code "57") (name "unconnected-(U4-NC-Pad42)") (class "Default")
      (node (ref "U4") (pin "42") (pinfunction "NC_42") (pintype "no_connect"))
    )
    (net (code "58") (name "unconnected-(U4-NC-Pad43)") (class "Default")
      (node (ref "U4") (pin "43") (pinfunction "NC_43") (pintype "no_connect"))
    )
    (net (code "59") (name "unconnected-(U4-STROBE-Pad27)") (class "Default")
      (node (ref "U4") (pin "27") (pinfunction "STROBE_27") (pintype "bidirectional"))
    )
  )
)
